# sensors.net
KiCad netlist of a schematic drawn in Altium Designer
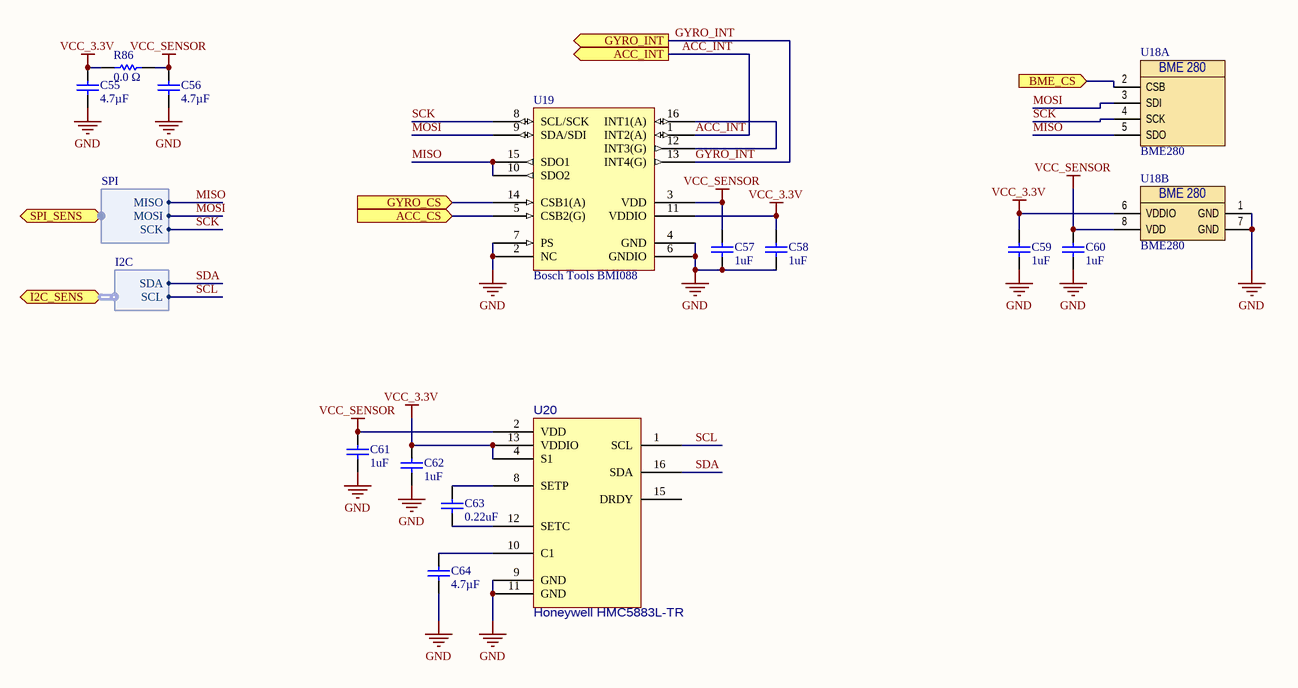
[diagram p0: sensors.SchDoc]

(export (version "E")
  (design (tool "Eeschema 10.0.6"))
  (components
    (comp (ref "C55")
      (value "4.7µF")
      (footprint "CAPC1608X90X35NL15T15")
      (description "0603 4.7 uF 10 V ±10 % Tolerance X5R SMT Multilayer Ceramic Capacitor")
      (libsource (lib "CommunityVault") (part "CAP-2"))
    )
    (comp (ref "C56")
      (value "4.7µF")
      (footprint "CAPC1608X90X35NL15T15")
      (description "0603 4.7 uF 10 V ±10 % Tolerance X5R SMT Multilayer Ceramic Capacitor")
      (libsource (lib "CommunityVault") (part "CAP-2"))
    )
    (comp (ref "C57")
      (value "1uF")
      (footprint "CAPC1005X56X25NL10T15")
      (description "Cap Ceramic 1uF 10V X5R 20% SMD 0402 85C Paper T/R")
      (fields (field (name "MANUFACTURER PART NUMBER") "0402ZD105MAT2A"))
      (libsource (lib "CommunityVault") (part "CMP-126963-2"))
    )
    (comp (ref "C58")
      (value "1uF")
      (footprint "CAPC1005X56X25NL10T15")
      (description "Cap Ceramic 1uF 10V X5R 20% SMD 0402 85C Paper T/R")
      (fields (field (name "MANUFACTURER PART NUMBER") "0402ZD105MAT2A"))
      (libsource (lib "CommunityVault") (part "CMP-126963-2"))
    )
    (comp (ref "C59")
      (value "1uF")
      (footprint "CAPC1005X56X25NL10T15")
      (description "Cap Ceramic 1uF 10V X5R 20% SMD 0402 85C Paper T/R")
      (fields (field (name "MANUFACTURER PART NUMBER") "0402ZD105MAT2A"))
      (libsource (lib "CommunityVault") (part "CMP-126963-2"))
    )
    (comp (ref "C60")
      (value "1uF")
      (footprint "CAPC1005X56X25NL10T15")
      (description "Cap Ceramic 1uF 10V X5R 20% SMD 0402 85C Paper T/R")
      (fields (field (name "MANUFACTURER PART NUMBER") "0402ZD105MAT2A"))
      (libsource (lib "CommunityVault") (part "CMP-126963-2"))
    )
    (comp (ref "C61")
      (value "1uF")
      (footprint "CAPC1005X56X25NL10T15")
      (description "Cap Ceramic 1uF 10V X5R 20% SMD 0402 85C Paper T/R")
      (fields (field (name "MANUFACTURER PART NUMBER") "0402ZD105MAT2A"))
      (libsource (lib "CommunityVault") (part "CMP-126963-2"))
    )
    (comp (ref "C62")
      (value "1uF")
      (footprint "CAPC1005X56X25NL10T15")
      (description "Cap Ceramic 1uF 10V X5R 20% SMD 0402 85C Paper T/R")
      (fields (field (name "MANUFACTURER PART NUMBER") "0402ZD105MAT2A"))
      (libsource (lib "CommunityVault") (part "CMP-126963-2"))
    )
    (comp (ref "C63")
      (value "0.22uF")
      (footprint "CAPC1005X56X25NL10T15")
      (description "AVX   04026D224KAT2A   CAP, MLCC, X5R, 220NF, 6.3V, 0402")
      (fields (field (name "MANUFACTURER PART NUMBER") "04026D224KAT2A"))
      (libsource (lib "CommunityVault") (part "CMP-126172-3"))
    )
    (comp (ref "C64")
      (value "4.7µF")
      (footprint "CAPC1608X90X35NL15T15")
      (description "0603 4.7 uF 10 V ±10 % Tolerance X5R SMT Multilayer Ceramic Capacitor")
      (libsource (lib "CommunityVault") (part "CAP-2"))
    )
    (comp (ref "R86")
      (value "0.0 Ω")
      (footprint "RESC1608X55X25LL10T15")
      (description "Thick Film Resistors - SMD ZERO OHM JUMPER")
      (libsource (lib "CommunityVault") (part "CMP-3661350-4"))
    )
    (comp (ref "U18")
      (value "BME280")
      (footprint "PCB-pz4u251hci7fplawf7tn-1")
      (description "Pressure, Temperature and Humidity Sensor Digital Output 1.8V 8-Pin LGA T/R")
      (libsource (lib "CommunityVault") (part "SYM-a1c26bef29297e05-3"))
    )
    (comp (ref "U19")
      (value "Bosch Tools BMI088")
      (footprint "PCB-rx9ouf6ws7u2trts4ghn-1")
      (description "BMI088 Series 3.6 V 6 Axis Digital Output Accelerometer Motion Sensor - LGA-16")
      (fields (field (name "MANUFACTURER PART NUMBER") "BMI088"))
      (libsource (lib "FavoritesLibrary") (part "SYM-3c8ff0f6eb07e348-1"))
    )
    (comp (ref "U20")
      (value "Honeywell HMC5883L-TR")
      (footprint "PCB-2968744-2")
      (description "MAGNETIC SENSOR ON TAPE AND REEL")
      (fields (field (name "MANUFACTURER PART NUMBER") "HMC5883L-TR"))
      (libsource (lib "CommunityVault") (part "SYM-2968744-2"))
    )
  )
  (nets
    (net (code "3") (name "/ACC_CS") (class "Default")
      (node (ref "U19") (pin "5") (pinfunction "CSB2(G)_5") (pintype "input"))
    )
    (net (code "4") (name "/ACC_INT") (class "Default")
      (node (ref "U19") (pin "1") (pinfunction "INT2(A)_1") (pintype "bidirectional"))
    )
    (net (code "5") (name "/BME_CS") (class "Default")
      (node (ref "U18") (pin "2") (pinfunction "CSB_2") (pintype "passive"))
    )
    (net (code "6") (name "/GYRO_CS") (class "Default")
      (node (ref "U19") (pin "14") (pinfunction "CSB1(A)_14") (pintype "input"))
    )
    (net (code "7") (name "/GYRO_INT") (class "Default")
      (node (ref "U19") (pin "13") (pinfunction "INT4(G)_13") (pintype "output"))
    )
    (net (code "8") (name "/MISO") (class "Default")
      (node (ref "U18") (pin "5") (pinfunction "SDO_5") (pintype "passive"))
      (node (ref "U19") (pin "10") (pinfunction "SDO2_10") (pintype "output"))
      (node (ref "U19") (pin "15") (pinfunction "SDO1_15") (pintype "output"))
    )
    (net (code "9") (name "/MOSI") (class "Default")
      (node (ref "U18") (pin "3") (pinfunction "SDI_3") (pintype "passive"))
      (node (ref "U19") (pin "9") (pinfunction "SDA/SDI_9") (pintype "bidirectional"))
    )
    (net (code "10") (name "/SCK") (class "Default")
      (node (ref "U18") (pin "4") (pinfunction "SCK_4") (pintype "passive"))
      (node (ref "U19") (pin "8") (pinfunction "SCL/SCK_8") (pintype "bidirectional"))
    )
    (net (code "11") (name "/SCL") (class "Default")
      (node (ref "U20") (pin "1") (pinfunction "SCL_1") (pintype "passive"))
    )
    (net (code "12") (name "/SDA") (class "Default")
      (node (ref "U20") (pin "16") (pinfunction "SDA_16") (pintype "passive"))
    )
    (net (code "15") (name "GND") (class "Default")
      (node (ref "C55") (pin "1") (pinfunction "1_1") (pintype "passive"))
      (node (ref "C56") (pin "1") (pinfunction "1_1") (pintype "passive"))
      (node (ref "C57") (pin "1") (pinfunction "1_1") (pintype "passive"))
      (node (ref "C58") (pin "1") (pinfunction "1_1") (pintype "passive"))
      (node (ref "C59") (pin "1") (pinfunction "1_1") (pintype "passive"))
      (node (ref "C60") (pin "1") (pinfunction "1_1") (pintype "passive"))
      (node (ref "C61") (pin "1") (pinfunction "1_1") (pintype "passive"))
      (node (ref "C62") (pin "1") (pinfunction "1_1") (pintype "passive"))
      (node (ref "C64") (pin "2") (pinfunction "2_2") (pintype "passive"))
      (node (ref "U18") (pin "1") (pinfunction "GND_1") (pintype "passive"))
      (node (ref "U18") (pin "7") (pinfunction "GND_7") (pintype "passive"))
      (node (ref "U19") (pin "2") (pinfunction "NC_2") (pintype "passive"))
      (node (ref "U19") (pin "4") (pinfunction "GND_4") (pintype "power_in"))
      (node (ref "U19") (pin "6") (pinfunction "GNDIO_6") (pintype "power_in"))
      (node (ref "U19") (pin "7") (pinfunction "PS_7") (pintype "input"))
      (node (ref "U20") (pin "11") (pinfunction "GND_11") (pintype "passive"))
      (node (ref "U20") (pin "9") (pinfunction "GND_9") (pintype "passive"))
    )
    (net (code "16") (name "Net-(U19-INT1(A))") (class "Default")
      (node (ref "U19") (pin "12") (pinfunction "INT3(G)_12") (pintype "output"))
      (node (ref "U19") (pin "16") (pinfunction "INT1(A)_16") (pintype "bidirectional"))
    )
    (net (code "17") (name "Net-(U20-C1)") (class "Default")
      (node (ref "C64") (pin "1") (pinfunction "1_1") (pintype "passive"))
      (node (ref "U20") (pin "10") (pinfunction "C1_10") (pintype "passive"))
    )
    (net (code "18") (name "Net-(U20-SETC)") (class "Default")
      (node (ref "C63") (pin "1") (pinfunction "1_1") (pintype "passive"))
      (node (ref "U20") (pin "12") (pinfunction "SETC_12") (pintype "passive"))
    )
    (net (code "19") (name "Net-(U20-SETP)") (class "Default")
      (node (ref "C63") (pin "2") (pinfunction "2_2") (pintype "passive"))
      (node (ref "U20") (pin "8") (pinfunction "SETP_8") (pintype "passive"))
    )
    (net (code "20") (name "VCC_3.3V") (class "Default")
      (node (ref "C55") (pin "2") (pinfunction "2_2") (pintype "passive"))
      (node (ref "C58") (pin "2") (pinfunction "2_2") (pintype "passive"))
      (node (ref "C59") (pin "2") (pinfunction "2_2") (pintype "passive"))
      (node (ref "C62") (pin "2") (pinfunction "2_2") (pintype "passive"))
      (node (ref "R86") (pin "2") (pinfunction "2_2") (pintype "passive"))
      (node (ref "U18") (pin "6") (pinfunction "VDDIO_6") (pintype "passive"))
      (node (ref "U19") (pin "11") (pinfunction "VDDIO_11") (pintype "power_in"))
      (node (ref "U20") (pin "13") (pinfunction "VDDIO_13") (pintype "passive"))
      (node (ref "U20") (pin "4") (pinfunction "S1_4") (pintype "passive"))
    )
    (net (code "21") (name "VCC_SENSOR") (class "Default")
      (node (ref "C56") (pin "2") (pinfunction "2_2") (pintype "passive"))
      (node (ref "C57") (pin "2") (pinfunction "2_2") (pintype "passive"))
      (node (ref "C60") (pin "2") (pinfunction "2_2") (pintype "passive"))
      (node (ref "C61") (pin "2") (pinfunction "2_2") (pintype "passive"))
      (node (ref "R86") (pin "1") (pinfunction "1_1") (pintype "passive"))
      (node (ref "U18") (pin "8") (pinfunction "VDD_8") (pintype "passive"))
      (node (ref "U19") (pin "3") (pinfunction "VDD_3") (pintype "power_in"))
      (node (ref "U20") (pin "2") (pinfunction "VDD_2") (pintype "passive"))
    )
    (net (code "22") (name "unconnected-(U20-DRDY-Pad15)") (class "Default")
      (node (ref "U20") (pin "15") (pinfunction "DRDY_15") (pintype "passive"))
    )
  )
)
